# P-S_0-30V_3A_Line.net
KiCad netlist of a schematic drawn in Altium Designer
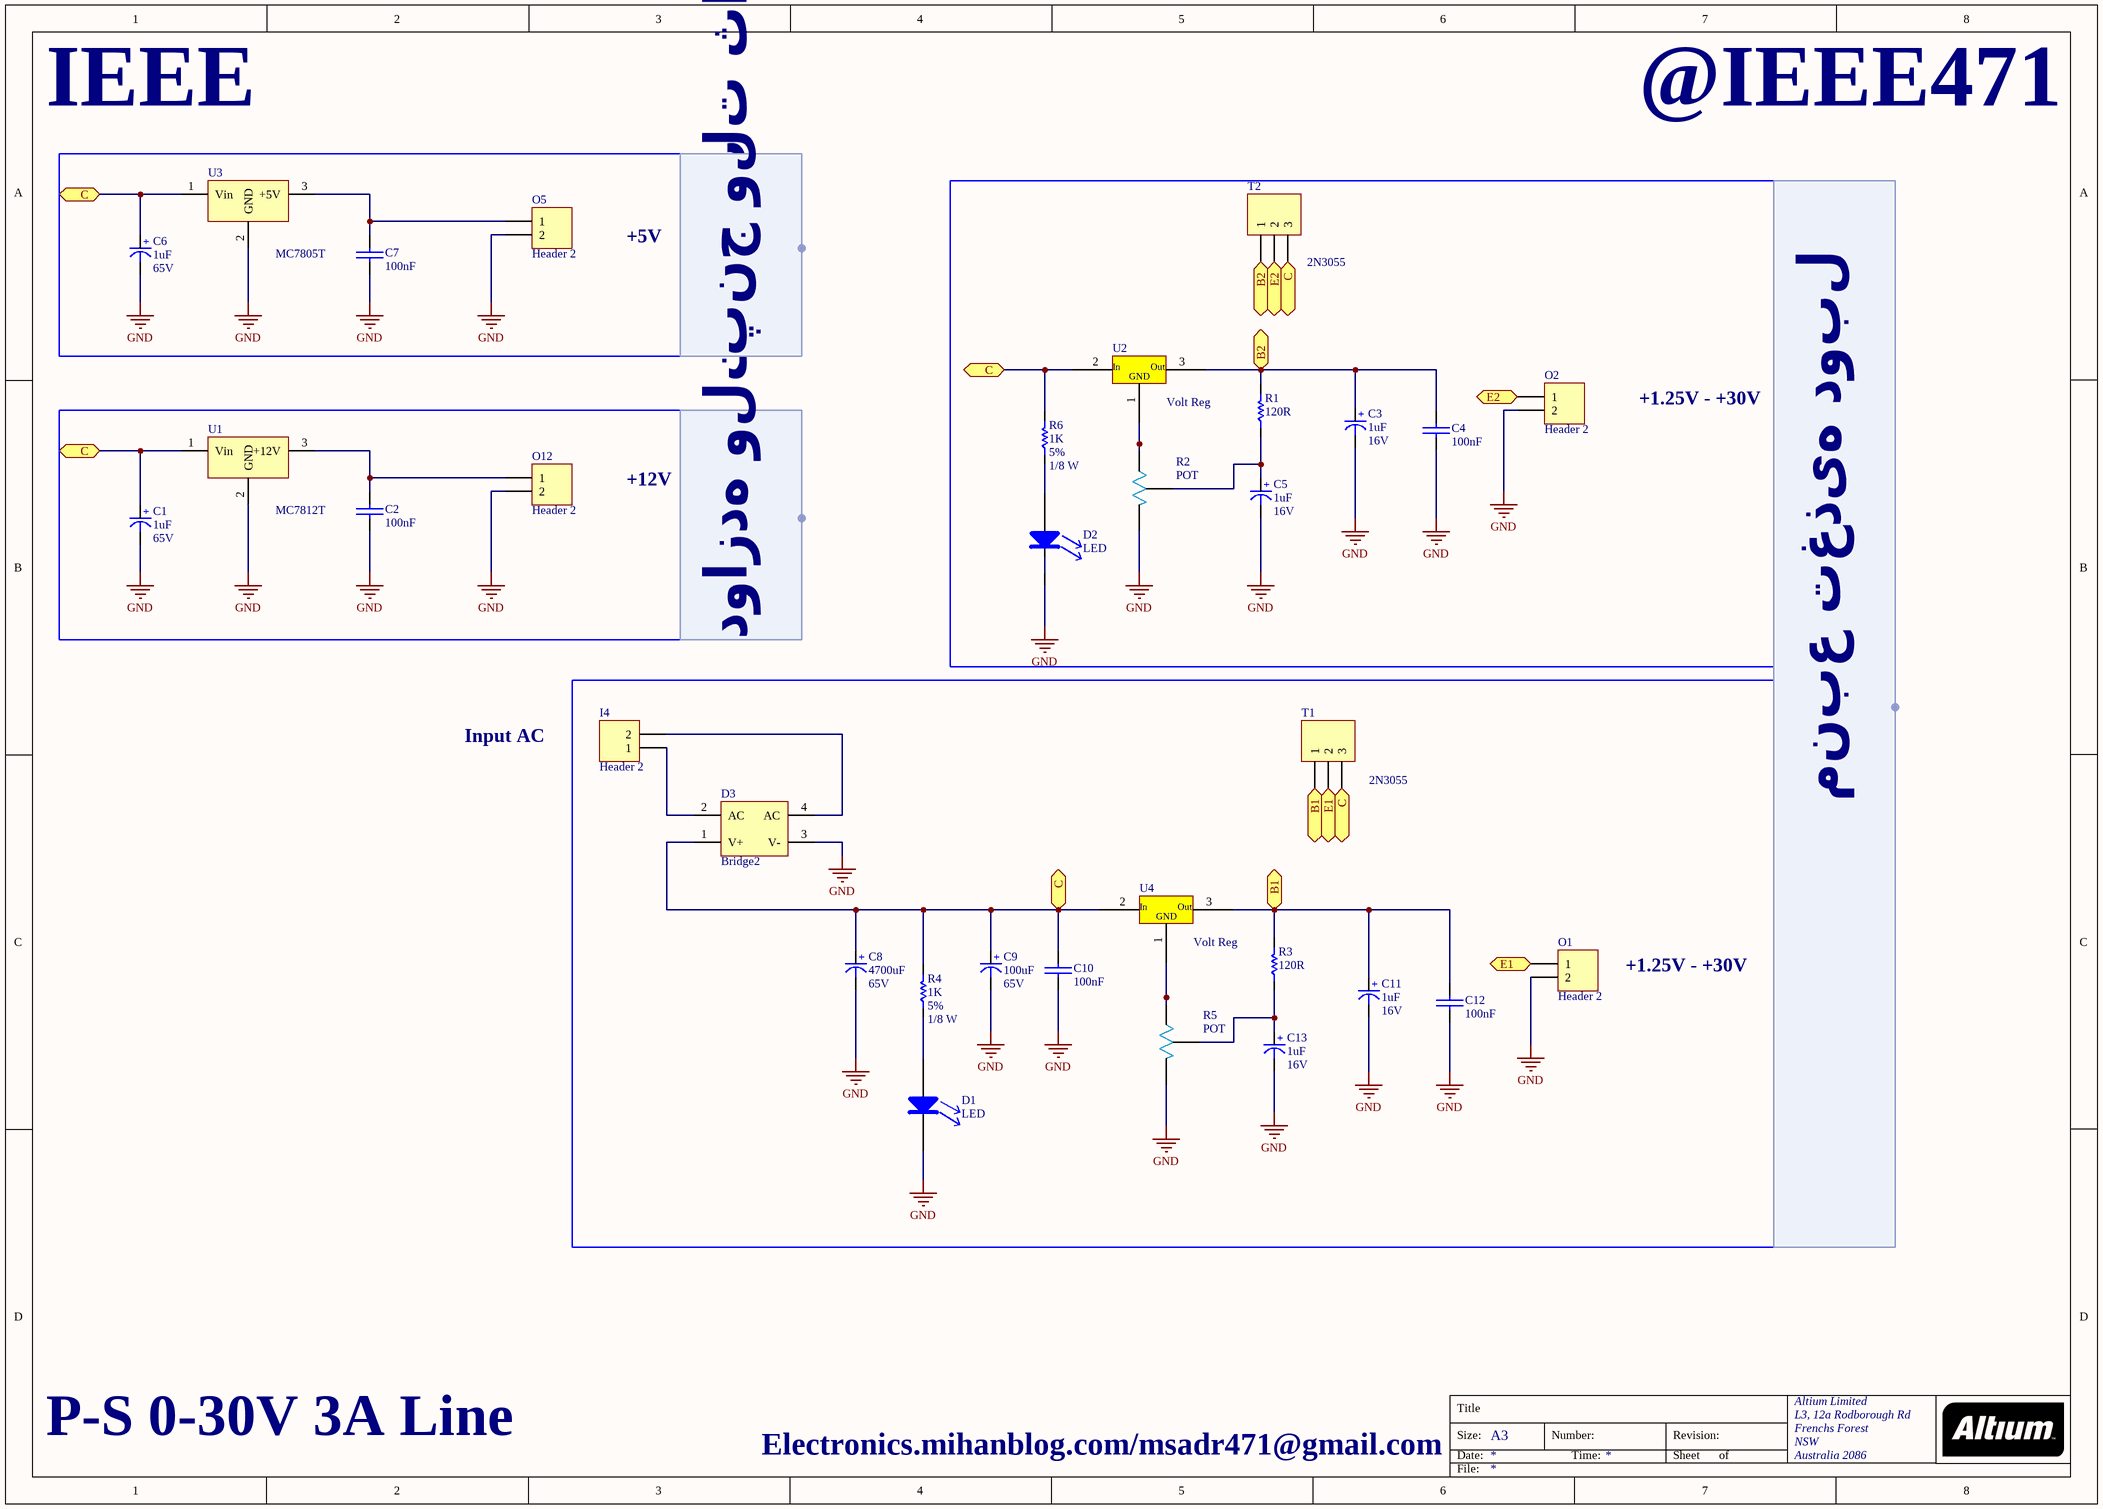
[diagram p0: P-S 0-30V 3A Line.SchDoc]

(export (version "E")
  (design (tool "Eeschema 10.0.6"))
  (components
    (comp (ref "C1")
      (value "1uF")
      (footprint "cap 02")
      (description "Polar Capacitor")
      (fields (field (name "VOLTAGE") "65V") (field (name "DESIGNER") "Saeid Jorablo"))
      (libsource (lib "My Library") (part "Cap-Polar"))
    )
    (comp (ref "C2")
      (value "100nF")
      (footprint "Cap - 100nF")
      (description "Bipolar Capacitor")
      (fields (field (name "VOLTAGE") "100V") (field (name "DESIGNER") "Saeid Jorablo"))
      (libsource (lib "My Library") (part "Cap-Bipolar"))
    )
    (comp (ref "C3")
      (value "1uF")
      (footprint "cap 02")
      (description "Polar Capacitor")
      (fields (field (name "VOLTAGE") "16V") (field (name "DESIGNER") "Saeid Jorablo"))
      (libsource (lib "My Library") (part "Cap-Polar"))
    )
    (comp (ref "C4")
      (value "100nF")
      (footprint "Cap - 100nF - 2")
      (description "Bipolar Capacitor")
      (fields (field (name "VOLTAGE") "100V") (field (name "DESIGNER") "Saeid Jorablo"))
      (libsource (lib "My Library") (part "Cap-Bipolar"))
    )
    (comp (ref "C5")
      (value "1uF")
      (footprint "cap 02")
      (description "Polar Capacitor")
      (fields (field (name "VOLTAGE") "16V") (field (name "DESIGNER") "Saeid Jorablo"))
      (libsource (lib "My Library") (part "Cap-Polar"))
    )
    (comp (ref "C6")
      (value "1uF")
      (footprint "cap 02")
      (description "Polar Capacitor")
      (fields (field (name "VOLTAGE") "65V") (field (name "DESIGNER") "Saeid Jorablo"))
      (libsource (lib "My Library") (part "Cap-Polar"))
    )
    (comp (ref "C7")
      (value "100nF")
      (footprint "Cap - 100nF")
      (description "Bipolar Capacitor")
      (fields (field (name "VOLTAGE") "100V") (field (name "DESIGNER") "Saeid Jorablo"))
      (libsource (lib "My Library") (part "Cap-Bipolar"))
    )
    (comp (ref "C8")
      (value "4700uF")
      (footprint "CAP 05")
      (description "Polar Capacitor")
      (fields
        (field (name "VOLTAGE") "65V")
        (field (name "Comment") "1uF")
        (field (name "DESIGNER") "Saeid Jorablo")
      )
      (libsource (lib "My Library") (part "Cap-Polar"))
    )
    (comp (ref "C9")
      (value "100uF")
      (footprint "cap 02")
      (description "Polar Capacitor")
      (fields
        (field (name "VOLTAGE") "65V")
        (field (name "Comment") "1uF")
        (field (name "DESIGNER") "Saeid Jorablo")
      )
      (libsource (lib "My Library") (part "Cap-Polar"))
    )
    (comp (ref "C10")
      (value "100nF")
      (footprint "Cap - 100nF - 2")
      (description "Bipolar Capacitor")
      (fields (field (name "VOLTAGE") "100V") (field (name "DESIGNER") "Saeid Jorablo"))
      (libsource (lib "My Library") (part "Cap-Bipolar"))
    )
    (comp (ref "C11")
      (value "1uF")
      (footprint "cap 02")
      (description "Polar Capacitor")
      (fields (field (name "VOLTAGE") "16V") (field (name "DESIGNER") "Saeid Jorablo"))
      (libsource (lib "My Library") (part "Cap-Polar"))
    )
    (comp (ref "C12")
      (value "100nF")
      (footprint "Cap - 100nF - 2")
      (description "Bipolar Capacitor")
      (fields (field (name "VOLTAGE") "100V") (field (name "DESIGNER") "Saeid Jorablo"))
      (libsource (lib "My Library") (part "Cap-Bipolar"))
    )
    (comp (ref "C13")
      (value "1uF")
      (footprint "cap 02")
      (description "Polar Capacitor")
      (fields (field (name "VOLTAGE") "16V") (field (name "DESIGNER") "Saeid Jorablo"))
      (libsource (lib "My Library") (part "Cap-Polar"))
    )
    (comp (ref "D1")
      (value "LED")
      (footprint "Blue LED 5mm")
      (fields (field (name "VOLTAGE") "3V"))
      (libsource (lib "Library") (part "LED Full color"))
    )
    (comp (ref "D2")
      (value "LED")
      (footprint "Blue LED 5mm")
      (fields (field (name "VOLTAGE") "3V"))
      (libsource (lib "Library") (part "LED Full color"))
    )
    (comp (ref "D3")
      (value "Bridge2")
      (footprint "D-46_6A")
      (description "Diode Bridge")
      (fields (field (name "PUBLISHER") "Altium Limited"))
      (libsource (lib "Miscellaneous Devices") (part "Bridge2"))
    )
    (comp (ref "I4")
      (value "Header 2")
      (footprint "HDR1X2")
      (description "Header, 2-Pin")
      (fields (field (name "PUBLISHER") "Altium Limited"))
      (libsource (lib "") (part "Header 2_1"))
    )
    (comp (ref "O1")
      (value "Header 2")
      (footprint "HDR1X2")
      (description "Header, 2-Pin")
      (fields (field (name "PUBLISHER") "Altium Limited"))
      (libsource (lib "Miscellaneous Connectors") (part "Header 2"))
    )
    (comp (ref "O2")
      (value "Header 2")
      (footprint "HDR1X2")
      (description "Header, 2-Pin")
      (fields (field (name "PUBLISHER") "Altium Limited"))
      (libsource (lib "Miscellaneous Connectors") (part "Header 2"))
    )
    (comp (ref "O5")
      (value "Header 2")
      (footprint "HDR1X2")
      (description "Header, 2-Pin")
      (fields (field (name "PUBLISHER") "Altium Limited"))
      (libsource (lib "Miscellaneous Connectors") (part "Header 2"))
    )
    (comp (ref "O12")
      (value "Header 2")
      (footprint "HDR1X2")
      (description "Header, 2-Pin")
      (fields (field (name "PUBLISHER") "Altium Limited"))
      (libsource (lib "Miscellaneous Connectors") (part "Header 2"))
    )
    (comp (ref "R1")
      (value "120R")
      (footprint "Res-(1/4)")
      (description "Resistor")
      (fields (field (name "TOLERANCE") "5%") (field (name "POWER") "1/8 W"))
      (libsource (lib "My Library") (part "Resistor"))
    )
    (comp (ref "R2") (value "POT") (footprint "VOL_1") (libsource (lib "My_lib") (part "POT")))
    (comp (ref "R3")
      (value "120R")
      (footprint "Res-(1/4)")
      (description "Resistor")
      (fields (field (name "TOLERANCE") "5%") (field (name "POWER") "1/8 W"))
      (libsource (lib "My Library") (part "Resistor"))
    )
    (comp (ref "R4")
      (value "1K")
      (footprint "Res-(1/4)")
      (description "Resistor")
      (fields (field (name "TOLERANCE") "5%") (field (name "POWER") "1/8 W"))
      (libsource (lib "My Library") (part "Resistor"))
    )
    (comp (ref "R5") (value "POT") (footprint "VOL_1") (libsource (lib "My_lib") (part "POT")))
    (comp (ref "R6")
      (value "1K")
      (footprint "Res-(1/4)")
      (description "Resistor")
      (fields (field (name "TOLERANCE") "5%") (field (name "POWER") "1/8 W"))
      (libsource (lib "My Library") (part "Resistor"))
    )
    (comp (ref "T1")
      (value "2N3055")
      (footprint "HDR1X3")
      (description "Header, 3-Pin")
      (fields (field (name "PUBLISHER") "Altium Limited"))
      (libsource (lib "Miscellaneous Connectors") (part "Header 3"))
    )
    (comp (ref "T2")
      (value "2N3055")
      (footprint "HDR1X3")
      (description "Header, 3-Pin")
      (fields (field (name "PUBLISHER") "Altium Limited"))
      (libsource (lib "Miscellaneous Connectors") (part "Header 3"))
    )
    (comp (ref "U1")
      (value "MC7812T")
      (footprint "TO220V")
      (libsource (lib "Protel DOS Schematic") (part "MC7812T"))
    )
    (comp (ref "U2")
      (value "Volt Reg")
      (footprint "TO220")
      (description "LM337")
      (libsource (lib "Library") (part "Volt reg 3"))
    )
    (comp (ref "U3")
      (value "MC7805T")
      (footprint "TO220V")
      (libsource (lib "Protel DOS Schematic") (part "MC7805T"))
    )
    (comp (ref "U4")
      (value "Volt Reg")
      (footprint "TO220")
      (description "LM337")
      (libsource (lib "Library") (part "Volt reg 3"))
    )
  )
  (nets
    (net (code "1") (name "/B1") (class "Default")
      (node (ref "C11") (pin "1") (pinfunction "+_1") (pintype "passive"))
      (node (ref "C12") (pin "1") (pinfunction "+_1") (pintype "passive"))
      (node (ref "R3") (pin "2") (pinfunction "2_2") (pintype "passive"))
      (node (ref "T1") (pin "1") (pinfunction "1_1") (pintype "passive"))
      (node (ref "U4") (pin "3") (pinfunction "3_3") (pintype "passive"))
    )
    (net (code "2") (name "/B2") (class "Default")
      (node (ref "C3") (pin "1") (pinfunction "+_1") (pintype "passive"))
      (node (ref "C4") (pin "1") (pinfunction "+_1") (pintype "passive"))
      (node (ref "R1") (pin "2") (pinfunction "2_2") (pintype "passive"))
      (node (ref "T2") (pin "1") (pinfunction "1_1") (pintype "passive"))
      (node (ref "U2") (pin "3") (pinfunction "3_3") (pintype "passive"))
    )
    (net (code "3") (name "/C") (class "Default")
      (node (ref "C1") (pin "1") (pinfunction "+_1") (pintype "passive"))
      (node (ref "C10") (pin "1") (pinfunction "+_1") (pintype "passive"))
      (node (ref "C6") (pin "1") (pinfunction "+_1") (pintype "passive"))
      (node (ref "C8") (pin "1") (pinfunction "+_1") (pintype "passive"))
      (node (ref "C9") (pin "1") (pinfunction "+_1") (pintype "passive"))
      (node (ref "D3") (pin "1") (pinfunction "V+_1") (pintype "passive"))
      (node (ref "R4") (pin "2") (pinfunction "2_2") (pintype "passive"))
      (node (ref "R6") (pin "2") (pinfunction "2_2") (pintype "passive"))
      (node (ref "T1") (pin "3") (pinfunction "3_3") (pintype "passive"))
      (node (ref "T2") (pin "3") (pinfunction "3_3") (pintype "passive"))
      (node (ref "U1") (pin "1") (pinfunction "Vin_1") (pintype "passive"))
      (node (ref "U2") (pin "2") (pinfunction "2_2") (pintype "passive"))
      (node (ref "U3") (pin "1") (pinfunction "Vin_1") (pintype "passive"))
      (node (ref "U4") (pin "2") (pinfunction "2_2") (pintype "passive"))
    )
    (net (code "4") (name "/E1") (class "Default")
      (node (ref "O1") (pin "1") (pinfunction "1_1") (pintype "passive"))
      (node (ref "T1") (pin "2") (pinfunction "2_2") (pintype "passive"))
    )
    (net (code "5") (name "/E2") (class "Default")
      (node (ref "O2") (pin "1") (pinfunction "1_1") (pintype "passive"))
      (node (ref "T2") (pin "2") (pinfunction "2_2") (pintype "passive"))
    )
    (net (code "6") (name "GND") (class "Default")
      (node (ref "C1") (pin "2") (pinfunction "-_2") (pintype "passive"))
      (node (ref "C10") (pin "2") (pinfunction "-_2") (pintype "passive"))
      (node (ref "C11") (pin "2") (pinfunction "-_2") (pintype "passive"))
      (node (ref "C12") (pin "2") (pinfunction "-_2") (pintype "passive"))
      (node (ref "C13") (pin "2") (pinfunction "-_2") (pintype "passive"))
      (node (ref "C2") (pin "2") (pinfunction "-_2") (pintype "passive"))
      (node (ref "C3") (pin "2") (pinfunction "-_2") (pintype "passive"))
      (node (ref "C4") (pin "2") (pinfunction "-_2") (pintype "passive"))
      (node (ref "C5") (pin "2") (pinfunction "-_2") (pintype "passive"))
      (node (ref "C6") (pin "2") (pinfunction "-_2") (pintype "passive"))
      (node (ref "C7") (pin "2") (pinfunction "-_2") (pintype "passive"))
      (node (ref "C8") (pin "2") (pinfunction "-_2") (pintype "passive"))
      (node (ref "C9") (pin "2") (pinfunction "-_2") (pintype "passive"))
      (node (ref "D1") (pin "2") (pinfunction "2_2") (pintype "passive"))
      (node (ref "D2") (pin "2") (pinfunction "2_2") (pintype "passive"))
      (node (ref "D3") (pin "3") (pinfunction "V-_3") (pintype "passive"))
      (node (ref "O1") (pin "2") (pinfunction "2_2") (pintype "passive"))
      (node (ref "O12") (pin "2") (pinfunction "2_2") (pintype "passive"))
      (node (ref "O2") (pin "2") (pinfunction "2_2") (pintype "passive"))
      (node (ref "O5") (pin "2") (pinfunction "2_2") (pintype "passive"))
      (node (ref "R2") (pin "3") (pintype "passive"))
      (node (ref "R5") (pin "3") (pintype "passive"))
      (node (ref "U1") (pin "2") (pinfunction "GND_2") (pintype "passive"))
      (node (ref "U3") (pin "2") (pinfunction "GND_2") (pintype "passive"))
    )
    (net (code "7") (name "Net-(C2-+)") (class "Default")
      (node (ref "C2") (pin "1") (pinfunction "+_1") (pintype "passive"))
      (node (ref "O12") (pin "1") (pinfunction "1_1") (pintype "passive"))
      (node (ref "U1") (pin "3") (pinfunction "+12V_3") (pintype "passive"))
    )
    (net (code "8") (name "Net-(C5-+)") (class "Default")
      (node (ref "C5") (pin "1") (pinfunction "+_1") (pintype "passive"))
      (node (ref "R1") (pin "1") (pinfunction "1_1") (pintype "passive"))
      (node (ref "R2") (pin "2") (pintype "passive"))
    )
    (net (code "9") (name "Net-(C7-+)") (class "Default")
      (node (ref "C7") (pin "1") (pinfunction "+_1") (pintype "passive"))
      (node (ref "O5") (pin "1") (pinfunction "1_1") (pintype "passive"))
      (node (ref "U3") (pin "3") (pinfunction "+5V_3") (pintype "passive"))
    )
    (net (code "10") (name "Net-(C13-+)") (class "Default")
      (node (ref "C13") (pin "1") (pinfunction "+_1") (pintype "passive"))
      (node (ref "R3") (pin "1") (pinfunction "1_1") (pintype "passive"))
      (node (ref "R5") (pin "2") (pintype "passive"))
    )
    (net (code "11") (name "Net-(D1-Pad1)") (class "Default")
      (node (ref "D1") (pin "1") (pinfunction "1_1") (pintype "passive"))
      (node (ref "R4") (pin "1") (pinfunction "1_1") (pintype "passive"))
    )
    (net (code "12") (name "Net-(D2-Pad1)") (class "Default")
      (node (ref "D2") (pin "1") (pinfunction "1_1") (pintype "passive"))
      (node (ref "R6") (pin "1") (pinfunction "1_1") (pintype "passive"))
    )
    (net (code "13") (name "Net-(D3-AC-Pad2)") (class "Default")
      (node (ref "D3") (pin "2") (pinfunction "AC_2") (pintype "passive"))
      (node (ref "I4") (pin "1") (pinfunction "1_1") (pintype "passive"))
    )
    (net (code "14") (name "Net-(D3-AC-Pad4)") (class "Default")
      (node (ref "D3") (pin "4") (pinfunction "AC_4") (pintype "passive"))
      (node (ref "I4") (pin "2") (pinfunction "2_2") (pintype "passive"))
    )
    (net (code "15") (name "Net-(R2-Pad1)") (class "Default")
      (node (ref "R2") (pin "1") (pintype "passive"))
      (node (ref "U2") (pin "1") (pinfunction "1_1") (pintype "passive"))
    )
    (net (code "16") (name "Net-(R5-Pad1)") (class "Default")
      (node (ref "R5") (pin "1") (pintype "passive"))
      (node (ref "U4") (pin "1") (pinfunction "1_1") (pintype "passive"))
    )
  )
)
